# mainBoard.net
KiCad netlist of a schematic drawn in EAGLE
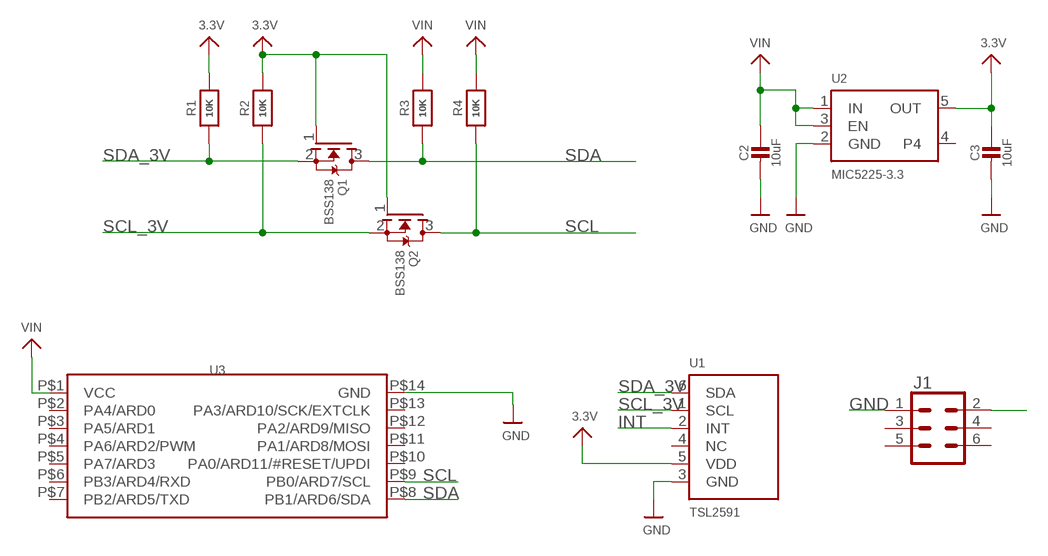
[diagram p0: schematic, sheet 1]

(export (version "E")
  (design (tool "Eeschema 10.0.6"))
  (components
    (comp (ref "C2")
      (value "10uF")
      (footprint "eagle-import:0805-NO")
      (libsource (lib "eagle-import") (part "CAP_CERAMIC0805-NOOUTLINE"))
    )
    (comp (ref "C3")
      (value "10uF")
      (footprint "eagle-import:0805-NO")
      (libsource (lib "eagle-import") (part "CAP_CERAMIC0805-NOOUTLINE"))
    )
    (comp (ref "J1")
      (value "CONN_03X22X3_SILK_MALE_PTH")
      (footprint "eagle-import:2X3")
      (libsource (lib "eagle-import") (part "CONN_03X22X3_SILK_MALE_PTH"))
    )
    (comp (ref "Q1")
      (value "BSS138")
      (footprint "eagle-import:SOT23-WIDE")
      (libsource (lib "eagle-import") (part "MOSFET-NWIDE"))
    )
    (comp (ref "Q2")
      (value "BSS138")
      (footprint "eagle-import:SOT23-WIDE")
      (libsource (lib "eagle-import") (part "MOSFET-NWIDE"))
    )
    (comp (ref "R1")
      (value "10K")
      (footprint "eagle-import:0805-NO")
      (libsource (lib "eagle-import") (part "RESISTOR0805_NOOUTLINE"))
    )
    (comp (ref "R2")
      (value "10K")
      (footprint "eagle-import:0805-NO")
      (libsource (lib "eagle-import") (part "RESISTOR0805_NOOUTLINE"))
    )
    (comp (ref "R3")
      (value "10K")
      (footprint "eagle-import:0805-NO")
      (libsource (lib "eagle-import") (part "RESISTOR0805_NOOUTLINE"))
    )
    (comp (ref "R4")
      (value "10K")
      (footprint "eagle-import:0805-NO")
      (libsource (lib "eagle-import") (part "RESISTOR0805_NOOUTLINE"))
    )
    (comp (ref "U1")
      (value "TSL2591")
      (footprint "eagle-import:DFN6_TAOS")
      (libsource (lib "eagle-import") (part "LIGHT_TSL2591"))
    )
    (comp (ref "U2")
      (value "MIC5225-3.3")
      (footprint "eagle-import:SOT23-5")
      (libsource (lib "eagle-import") (part "VREG_SOT23-5"))
    )
    (comp (ref "U3")
      (value "ATTINY1604")
      (footprint "eagle-import:SOIC150")
      (libsource (lib "eagle-import") (part "ATTINY1604"))
    )
  )
  (nets
    (net (code "1") (name "/INT") (class "Default")
      (node (ref "U1") (pin "2") (pinfunction "INT_2") (pintype "output"))
    )
    (net (code "2") (name "/SCL") (class "Default")
      (node (ref "Q2") (pin "3") (pinfunction "D_3") (pintype "bidirectional"))
      (node (ref "R4") (pin "1") (pinfunction "1_1") (pintype "passive"))
      (node (ref "U3") (pin "P$9") (pinfunction "PB0/ARD7/SCL_P$9") (pintype "bidirectional"))
    )
    (net (code "3") (name "/SCL_3V") (class "Default")
      (node (ref "Q2") (pin "2") (pinfunction "S_2") (pintype "bidirectional"))
      (node (ref "R2") (pin "1") (pinfunction "1_1") (pintype "passive"))
      (node (ref "U1") (pin "1") (pinfunction "SCL_1") (pintype "bidirectional"))
    )
    (net (code "4") (name "/SDA") (class "Default")
      (node (ref "Q1") (pin "3") (pinfunction "D_3") (pintype "bidirectional"))
      (node (ref "R3") (pin "1") (pinfunction "1_1") (pintype "passive"))
      (node (ref "U3") (pin "P$8") (pinfunction "PB1/ARD6/SDA_P$8") (pintype "bidirectional"))
    )
    (net (code "5") (name "/SDA_3V") (class "Default")
      (node (ref "Q1") (pin "2") (pinfunction "S_2") (pintype "bidirectional"))
      (node (ref "R1") (pin "1") (pinfunction "1_1") (pintype "passive"))
      (node (ref "U1") (pin "6") (pinfunction "SDA_6") (pintype "bidirectional"))
    )
    (net (code "6") (name "3.3V") (class "Default")
      (node (ref "C3") (pin "1") (pinfunction "1_1") (pintype "passive"))
      (node (ref "Q1") (pin "1") (pinfunction "G_1") (pintype "bidirectional"))
      (node (ref "Q2") (pin "1") (pinfunction "G_1") (pintype "bidirectional"))
      (node (ref "R1") (pin "2") (pinfunction "2_2") (pintype "passive"))
      (node (ref "R2") (pin "2") (pinfunction "2_2") (pintype "passive"))
      (node (ref "U1") (pin "5") (pinfunction "VDD_5") (pintype "power_in"))
      (node (ref "U2") (pin "5") (pinfunction "OUT_5") (pintype "power_in"))
    )
    (net (code "7") (name "GND") (class "Default")
      (node (ref "C2") (pin "2") (pinfunction "2_2") (pintype "passive"))
      (node (ref "C3") (pin "2") (pinfunction "2_2") (pintype "passive"))
      (node (ref "J1") (pin "1") (pinfunction "1_1") (pintype "bidirectional"))
      (node (ref "U1") (pin "3") (pinfunction "GND_3") (pintype "power_in"))
      (node (ref "U2") (pin "2") (pinfunction "GND_2") (pintype "power_in"))
      (node (ref "U3") (pin "P$14") (pinfunction "GND_P$14") (pintype "bidirectional"))
    )
    (net (code "8") (name "VIN") (class "Default")
      (node (ref "C2") (pin "1") (pinfunction "1_1") (pintype "passive"))
      (node (ref "J1") (pin "2") (pinfunction "2_2") (pintype "bidirectional"))
      (node (ref "R3") (pin "2") (pinfunction "2_2") (pintype "passive"))
      (node (ref "R4") (pin "2") (pinfunction "2_2") (pintype "passive"))
      (node (ref "U2") (pin "1") (pinfunction "IN_1") (pintype "power_in"))
      (node (ref "U2") (pin "3") (pinfunction "EN_3") (pintype "input"))
      (node (ref "U3") (pin "P$1") (pinfunction "VCC_P$1") (pintype "power_in"))
    )
    (net (code "9") (name "unconnected-(J1-Pad3)") (class "Default")
      (node (ref "J1") (pin "3") (pinfunction "3_3") (pintype "bidirectional"))
    )
    (net (code "10") (name "unconnected-(J1-Pad4)") (class "Default")
      (node (ref "J1") (pin "4") (pinfunction "4_4") (pintype "bidirectional"))
    )
    (net (code "11") (name "unconnected-(J1-Pad5)") (class "Default")
      (node (ref "J1") (pin "5") (pinfunction "5_5") (pintype "bidirectional"))
    )
    (net (code "12") (name "unconnected-(J1-Pad6)") (class "Default")
      (node (ref "J1") (pin "6") (pinfunction "6_6") (pintype "bidirectional"))
    )
    (net (code "13") (name "unconnected-(U1-NC-Pad4)") (class "Default")
      (node (ref "U1") (pin "4") (pinfunction "NC_4") (pintype "no_connect"))
    )
    (net (code "14") (name "unconnected-(U2-P4-Pad4)") (class "Default")
      (node (ref "U2") (pin "4") (pinfunction "P4_4") (pintype "bidirectional"))
    )
    (net (code "15") (name "unconnected-(U3-PA0{slash}ARD11{slash}#RESET{slash}UPDI-PadP$10)") (class "Default")
      (node (ref "U3") (pin "P$10") (pinfunction "PA0/ARD11/#RESET/UPDI_P$10") (pintype "bidirectional"))
    )
    (net (code "16") (name "unconnected-(U3-PA1{slash}ARD8{slash}MOSI-PadP$11)") (class "Default")
      (node (ref "U3") (pin "P$11") (pinfunction "PA1/ARD8/MOSI_P$11") (pintype "bidirectional"))
    )
    (net (code "17") (name "unconnected-(U3-PA2{slash}ARD9{slash}MISO-PadP$12)") (class "Default")
      (node (ref "U3") (pin "P$12") (pinfunction "PA2/ARD9/MISO_P$12") (pintype "bidirectional"))
    )
    (net (code "18") (name "unconnected-(U3-PA3{slash}ARD10{slash}SCK{slash}EXTCLK-PadP$13)") (class "Default")
      (node (ref "U3") (pin "P$13") (pinfunction "PA3/ARD10/SCK/EXTCLK_P$13") (pintype "bidirectional"))
    )
    (net (code "19") (name "unconnected-(U3-PA4{slash}ARD0-PadP$2)") (class "Default")
      (node (ref "U3") (pin "P$2") (pinfunction "PA4/ARD0_P$2") (pintype "bidirectional"))
    )
    (net (code "20") (name "unconnected-(U3-PA5{slash}ARD1-PadP$3)") (class "Default")
      (node (ref "U3") (pin "P$3") (pinfunction "PA5/ARD1_P$3") (pintype "bidirectional"))
    )
    (net (code "21") (name "unconnected-(U3-PA6{slash}ARD2{slash}PWM-PadP$4)") (class "Default")
      (node (ref "U3") (pin "P$4") (pinfunction "PA6/ARD2/PWM_P$4") (pintype "bidirectional"))
    )
    (net (code "22") (name "unconnected-(U3-PA7{slash}ARD3-PadP$5)") (class "Default")
      (node (ref "U3") (pin "P$5") (pinfunction "PA7/ARD3_P$5") (pintype "bidirectional"))
    )
    (net (code "23") (name "unconnected-(U3-PB2{slash}ARD5{slash}TXD-PadP$7)") (class "Default")
      (node (ref "U3") (pin "P$7") (pinfunction "PB2/ARD5/TXD_P$7") (pintype "bidirectional"))
    )
    (net (code "24") (name "unconnected-(U3-PB3{slash}ARD4{slash}RXD-PadP$6)") (class "Default")
      (node (ref "U3") (pin "P$6") (pinfunction "PB3/ARD4/RXD_P$6") (pintype "bidirectional"))
    )
  )
)
